# 09_Misc.net
KiCad netlist of a schematic drawn in Altium Designer
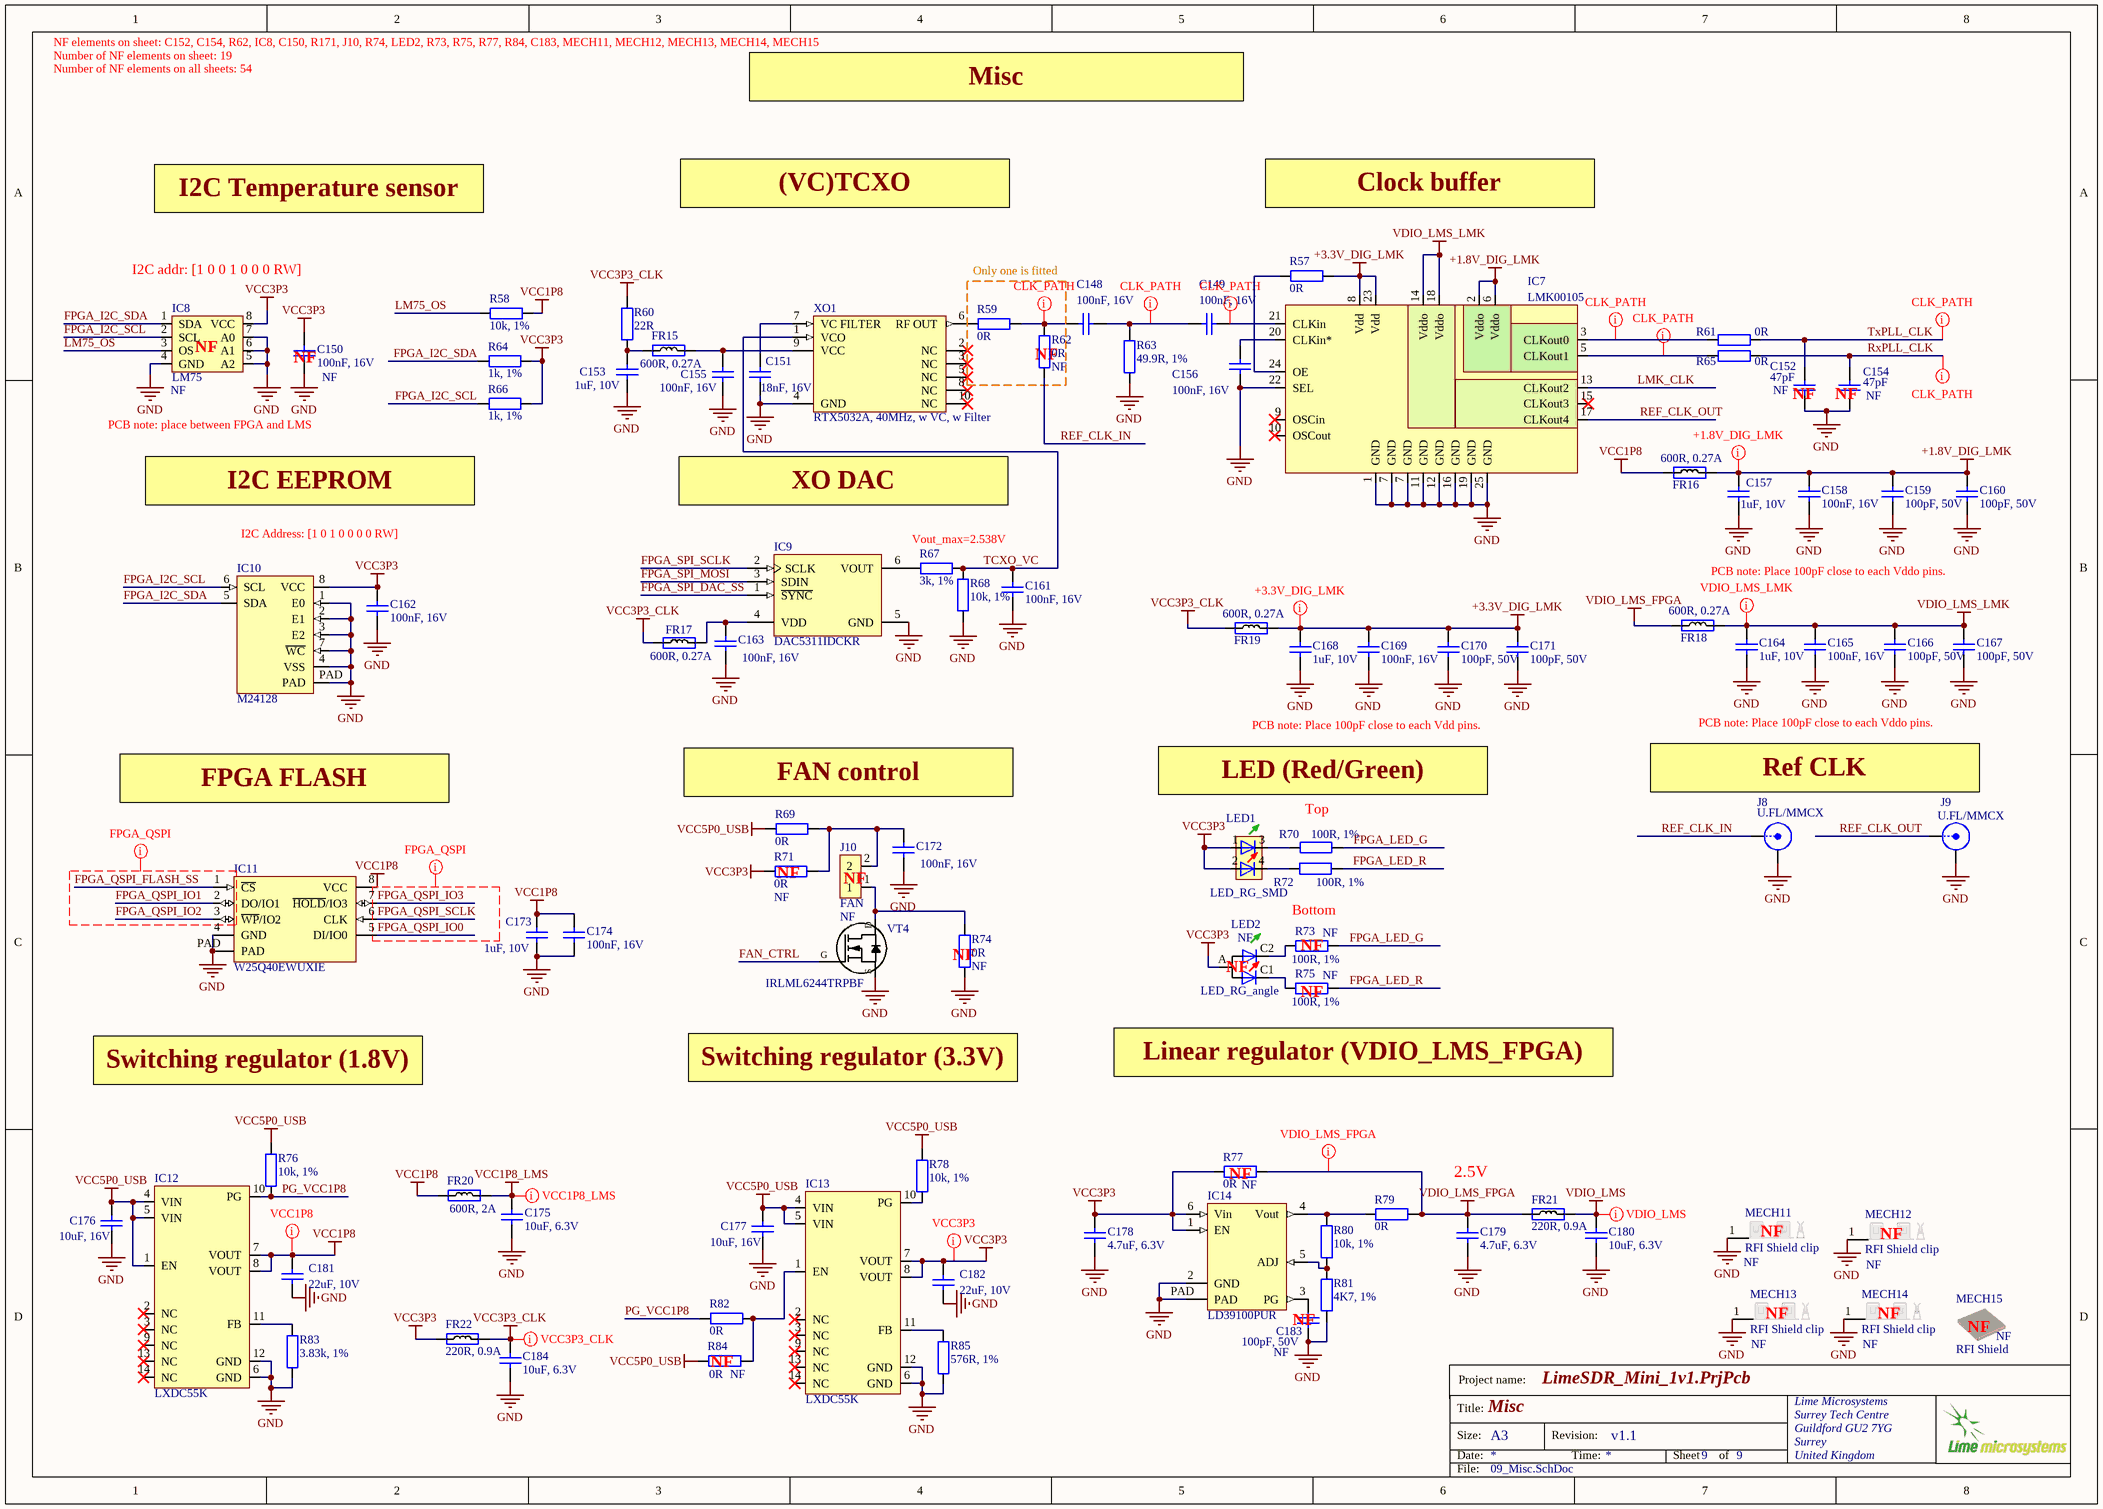
[diagram p0: 09_Misc.SchDoc]

(export (version "E")
  (design (tool "Eeschema 10.0.6"))
  (components
    (comp (ref "C148")
      (value "100nF, 16V")
      (footprint "CAP0402")
      (fields
        (field (name "MANUFACTURER") "Murata Electronics")
        (field (name "TOLERANCE") "10 %")
        (field (name "MANUFACTURER PART NUMBER") "GRM155R71C104KA88D")
      )
      (libsource (lib "LimeMicroAltiumLib_schLib") (part "Cap_0402"))
    )
    (comp (ref "C149")
      (value "100nF, 16V")
      (footprint "CAP0402")
      (fields
        (field (name "MANUFACTURER") "Murata Electronics")
        (field (name "TOLERANCE") "10 %")
        (field (name "MANUFACTURER PART NUMBER") "GRM155R71C104KA88D")
      )
      (libsource (lib "LimeMicroAltiumLib_schLib") (part "Cap_0402"))
    )
    (comp (ref "C150")
      (value "100nF, 16V")
      (footprint "CAP0402")
      (fields
        (field (name "TOLERANCE") "10 %")
        (field (name "MANUFACTURER") "Murata Electronics")
        (field (name "MANUFACTURER PART NUMBER") "GRM155R71C104KA88D")
        (field (name "ASSEMBLY INFO") "NF")
      )
      (libsource (lib "LimeFPGAboard_schLib") (part "Cap_0603"))
    )
    (comp (ref "C151")
      (value "18nF, 16V")
      (footprint "CAP0402")
      (fields (field (name "MANUFACTURER") "Yageo") (field (name "TOLERANCE") "±10%"))
      (libsource (lib "LimeMicroAltiumLib_schLib") (part "Cap_0402"))
    )
    (comp (ref "C152")
      (value "47pF")
      (footprint "CAP0402")
      (fields
        (field (name "TOLERANCE") "±1%")
        (field (name "MANUFACTURER") "TDK Corporation")
        (field (name "ASSEMBLY INFO") "NF")
      )
      (libsource (lib "LimeMicroAltiumLib_schLib") (part "Cap_0402"))
    )
    (comp (ref "C153")
      (value "1uF, 10V")
      (footprint "CAP0402")
      (fields (field (name "MANUFACTURER") "TDK"))
      (libsource (lib "LimeMicroAltiumLib_schLib") (part "Cap_0402"))
    )
    (comp (ref "C154")
      (value "47pF")
      (footprint "CAP0402")
      (fields
        (field (name "TOLERANCE") "±1%")
        (field (name "MANUFACTURER") "TDK Corporation")
        (field (name "ASSEMBLY INFO") "NF")
      )
      (libsource (lib "LimeMicroAltiumLib_schLib") (part "Cap_0402"))
    )
    (comp (ref "C155")
      (value "100nF, 16V")
      (footprint "CAP0402")
      (fields
        (field (name "MANUFACTURER") "Murata Electronics")
        (field (name "TOLERANCE") "10 %")
        (field (name "MANUFACTURER PART NUMBER") "GRM155R71C104KA88D")
      )
      (libsource (lib "LimeMicroAltiumLib_schLib") (part "Cap_0402"))
    )
    (comp (ref "C156")
      (value "100nF, 16V")
      (footprint "CAP0402")
      (fields
        (field (name "MANUFACTURER") "Murata Electronics")
        (field (name "TOLERANCE") "10 %")
        (field (name "MANUFACTURER PART NUMBER") "GRM155R71C104KA88D")
      )
      (libsource (lib "LimeMicroAltiumLib_schLib") (part "Cap_0402"))
    )
    (comp (ref "C157")
      (value "1uF, 10V")
      (footprint "CAP0402")
      (fields (field (name "MANUFACTURER") "TDK"))
      (libsource (lib "LimeMicroAltiumLib_schLib") (part "Cap_0402"))
    )
    (comp (ref "C158")
      (value "100nF, 16V")
      (footprint "CAP0402")
      (fields
        (field (name "MANUFACTURER") "Murata Electronics")
        (field (name "TOLERANCE") "10 %")
        (field (name "MANUFACTURER PART NUMBER") "GRM155R71C104KA88D")
      )
      (libsource (lib "LimeMicroAltiumLib_schLib") (part "Cap_0402"))
    )
    (comp (ref "C159")
      (value "100pF, 50V")
      (footprint "CAP0402")
      (fields (field (name "MANUFACTURER") "Yageo") (field (name "TOLERANCE") "±5%"))
      (libsource (lib "LimeMicroAltiumLib_schLib") (part "Cap_0402"))
    )
    (comp (ref "C160")
      (value "100pF, 50V")
      (footprint "CAP0402")
      (fields (field (name "MANUFACTURER") "Yageo") (field (name "TOLERANCE") "±5%"))
      (libsource (lib "LimeMicroAltiumLib_schLib") (part "Cap_0402"))
    )
    (comp (ref "C161")
      (value "100nF, 16V")
      (footprint "CAP0402")
      (fields
        (field (name "MANUFACTURER") "Murata Electronics")
        (field (name "TOLERANCE") "10 %")
        (field (name "MANUFACTURER PART NUMBER") "GRM155R71C104KA88D")
      )
      (libsource (lib "LimeMicroAltiumLib_schLib") (part "Cap_0402"))
    )
    (comp (ref "C162")
      (value "100nF, 16V")
      (footprint "CAP0402")
      (fields
        (field (name "TOLERANCE") "10 %")
        (field (name "MANUFACTURER") "Murata Electronics")
        (field (name "MANUFACTURER PART NUMBER") "GRM155R71C104KA88D")
      )
      (libsource (lib "LimeFPGAboard_schLib") (part "Cap_0603"))
    )
    (comp (ref "C163")
      (value "100nF, 16V")
      (footprint "CAP0402")
      (fields
        (field (name "TOLERANCE") "10 %")
        (field (name "MANUFACTURER") "Murata Electronics")
        (field (name "MANUFACTURER PART NUMBER") "GRM155R71C104KA88D")
      )
      (libsource (lib "LimeFPGAboard_schLib") (part "Cap_0603"))
    )
    (comp (ref "C164")
      (value "1uF, 10V")
      (footprint "CAP0402")
      (fields (field (name "MANUFACTURER") "TDK"))
      (libsource (lib "LimeMicroAltiumLib_schLib") (part "Cap_0402"))
    )
    (comp (ref "C165")
      (value "100nF, 16V")
      (footprint "CAP0402")
      (fields
        (field (name "MANUFACTURER") "Murata Electronics")
        (field (name "TOLERANCE") "10 %")
        (field (name "MANUFACTURER PART NUMBER") "GRM155R71C104KA88D")
      )
      (libsource (lib "LimeMicroAltiumLib_schLib") (part "Cap_0402"))
    )
    (comp (ref "C166")
      (value "100pF, 50V")
      (footprint "CAP0402")
      (fields (field (name "MANUFACTURER") "Yageo") (field (name "TOLERANCE") "±5%"))
      (libsource (lib "LimeMicroAltiumLib_schLib") (part "Cap_0402"))
    )
    (comp (ref "C167")
      (value "100pF, 50V")
      (footprint "CAP0402")
      (fields (field (name "MANUFACTURER") "Yageo") (field (name "TOLERANCE") "±5%"))
      (libsource (lib "LimeMicroAltiumLib_schLib") (part "Cap_0402"))
    )
    (comp (ref "C168")
      (value "1uF, 10V")
      (footprint "CAP0402")
      (fields (field (name "MANUFACTURER") "TDK"))
      (libsource (lib "LimeMicroAltiumLib_schLib") (part "Cap_0402"))
    )
    (comp (ref "C169")
      (value "100nF, 16V")
      (footprint "CAP0402")
      (fields
        (field (name "MANUFACTURER") "Murata Electronics")
        (field (name "TOLERANCE") "10 %")
        (field (name "MANUFACTURER PART NUMBER") "GRM155R71C104KA88D")
      )
      (libsource (lib "LimeMicroAltiumLib_schLib") (part "Cap_0402"))
    )
    (comp (ref "C170")
      (value "100pF, 50V")
      (footprint "CAP0402")
      (fields (field (name "MANUFACTURER") "Yageo") (field (name "TOLERANCE") "±5%"))
      (libsource (lib "LimeMicroAltiumLib_schLib") (part "Cap_0402"))
    )
    (comp (ref "C171")
      (value "100pF, 50V")
      (footprint "CAP0402")
      (fields (field (name "MANUFACTURER") "Yageo") (field (name "TOLERANCE") "±5%"))
      (libsource (lib "LimeMicroAltiumLib_schLib") (part "Cap_0402"))
    )
    (comp (ref "C172")
      (value "100nF, 16V")
      (footprint "CAP0402")
      (fields
        (field (name "TOLERANCE") "10 %")
        (field (name "MANUFACTURER") "Murata Electronics")
        (field (name "MANUFACTURER PART NUMBER") "GRM155R71C104KA88D")
      )
      (libsource (lib "LimeFPGAboard_schLib") (part "Cap_0603"))
    )
    (comp (ref "C173")
      (value "1uF, 10V")
      (footprint "CAP0402")
      (fields (field (name "MANUFACTURER") "TDK"))
      (libsource (lib "LimeMicroAltiumLib_schLib") (part "Cap_0402"))
    )
    (comp (ref "C174")
      (value "100nF, 16V")
      (footprint "CAP0402")
      (fields
        (field (name "TOLERANCE") "10 %")
        (field (name "MANUFACTURER") "Murata Electronics")
        (field (name "MANUFACTURER PART NUMBER") "GRM155R71C104KA88D")
      )
      (libsource (lib "LimeFPGAboard_schLib") (part "Cap_0603"))
    )
    (comp (ref "C175")
      (value "10uF, 6.3V")
      (footprint "CAP0603")
      (fields (field (name "TOLERANCE") "±20%") (field (name "MANUFACTURER") "Yageo"))
      (libsource (lib "LimeFPGAboard_schLib") (part "Cap_0603"))
    )
    (comp (ref "C176")
      (value "10uF, 16V")
      (footprint "CAP0603")
      (fields (field (name "MANUFACTURER") "Yageo") (field (name "TOLERANCE") "±20%"))
      (libsource (lib "LimeMicroAltiumLib_schLib") (part "Cap_0603"))
    )
    (comp (ref "C177")
      (value "10uF, 16V")
      (footprint "CAP0603")
      (fields (field (name "MANUFACTURER") "Yageo") (field (name "TOLERANCE") "±20%"))
      (libsource (lib "LimeMicroAltiumLib_schLib") (part "Cap_0603"))
    )
    (comp (ref "C178")
      (value "4.7uF, 6.3V")
      (footprint "CAP0402")
      (fields
        (field (name "MANUFACTURER") "Murata Electronics North America")
        (field (name "TOLERANCE") "±20%")
        (field (name "MANUFACTURER PART NUMBER") "GRM155R60J475ME87D")
      )
      (libsource (lib "LimeMicroAltiumLib_schLib") (part "Cap_0402"))
    )
    (comp (ref "C179")
      (value "4.7uF, 6.3V")
      (footprint "CAP0402")
      (fields
        (field (name "MANUFACTURER") "Murata Electronics North America")
        (field (name "TOLERANCE") "±20%")
        (field (name "MANUFACTURER PART NUMBER") "GRM155R60J475ME87D")
      )
      (libsource (lib "LimeMicroAltiumLib_schLib") (part "Cap_0402"))
    )
    (comp (ref "C180")
      (value "10uF, 6.3V")
      (footprint "CAP0603")
      (fields (field (name "TOLERANCE") "±20%") (field (name "MANUFACTURER") "Yageo"))
      (libsource (lib "LimeFPGAboard_schLib") (part "Cap_0603"))
    )
    (comp (ref "C181")
      (value "22uF, 10V")
      (footprint "CAP0603")
      (fields (field (name "TOLERANCE") "20 %") (field (name "MANUFACTURER") "TDK Corporation"))
      (libsource (lib "LimeFPGAboard_schLib") (part "Cap_0603"))
    )
    (comp (ref "C182")
      (value "22uF, 10V")
      (footprint "CAP0603")
      (fields (field (name "TOLERANCE") "20 %") (field (name "MANUFACTURER") "TDK Corporation"))
      (libsource (lib "LimeFPGAboard_schLib") (part "Cap_0603"))
    )
    (comp (ref "C183")
      (value "100pF, 50V")
      (footprint "CAP0402")
      (fields
        (field (name "ASSEMBLY INFO") "NF")
        (field (name "MANUFACTURER") "Yageo")
        (field (name "TOLERANCE") "±5%")
      )
      (libsource (lib "LimeMicroAltiumLib_schLib") (part "Cap_0402"))
    )
    (comp (ref "C184")
      (value "10uF, 6.3V")
      (footprint "CAP0603")
      (fields (field (name "TOLERANCE") "±20%") (field (name "MANUFACTURER") "Yageo"))
      (libsource (lib "LimeFPGAboard_schLib") (part "Cap_0603"))
    )
    (comp (ref "FR15")
      (value "600R, 0.27A")
      (footprint "RES0201")
      (fields (field (name "MANUFACTURER") "Taiyo Yuden"))
      (libsource (lib "LimeMicroAltiumLib_schLib") (part "Ferrite"))
    )
    (comp (ref "FR16")
      (value "600R, 0.27A")
      (footprint "RES0201")
      (fields (field (name "MANUFACTURER") "Taiyo Yuden"))
      (libsource (lib "LimeMicroAltiumLib_schLib") (part "Ferrite"))
    )
    (comp (ref "FR17")
      (value "600R, 0.27A")
      (footprint "RES0201")
      (fields (field (name "MANUFACTURER") "Taiyo Yuden"))
      (libsource (lib "LimeMicroAltiumLib_schLib") (part "Ferrite"))
    )
    (comp (ref "FR18")
      (value "600R, 0.27A")
      (footprint "RES0201")
      (fields (field (name "MANUFACTURER") "Taiyo Yuden"))
      (libsource (lib "LimeMicroAltiumLib_schLib") (part "Ferrite"))
    )
    (comp (ref "FR19")
      (value "600R, 0.27A")
      (footprint "RES0201")
      (fields (field (name "MANUFACTURER") "Taiyo Yuden"))
      (libsource (lib "LimeMicroAltiumLib_schLib") (part "Ferrite"))
    )
    (comp (ref "FR20")
      (value "600R, 2A")
      (footprint "RES0805")
      (fields (field (name "MANUFACTURER") "TDK Corporation"))
      (libsource (lib "LimeMicroAltiumLib_schLib") (part "Ferrite"))
    )
    (comp (ref "FR21")
      (value "220R, 0.9A")
      (footprint "RES0402")
      (fields (field (name "MANUFACTURER") "TDK Corporation"))
      (libsource (lib "LimeFPGAboard_schLib") (part "Ferrite"))
    )
    (comp (ref "FR22")
      (value "220R, 0.9A")
      (footprint "RES0402")
      (fields (field (name "MANUFACTURER") "TDK Corporation"))
      (libsource (lib "LimeFPGAboard_schLib") (part "Ferrite"))
    )
    (comp (ref "IC7")
      (value "LMK00105")
      (footprint "LMK00105SQ")
      (fields (field (name "MANUFACTURER") "Texas Instruments"))
      (libsource (lib "LimeMicroAltiumLib_schLib") (part "LMK00105"))
    )
    (comp (ref "IC8")
      (value "LM75")
      (footprint "HWSON8_LM75")
      (fields
        (field (name "MANUFACTURER") "NXP Semiconductors")
        (field (name "MANUFACTURER PART NUMBER") "LM75BTP,147")
        (field (name "ASSEMBLY INFO") "NF")
      )
      (libsource (lib "LimeMicroAltiumLib_schLib") (part "LM75"))
    )
    (comp (ref "IC9")
      (value "DAC5311IDCKR")
      (footprint "AD5601_SOT23-6")
      (fields (field (name "MANUFACTURER") "Texas Instruments"))
      (libsource (lib "LimeMicroAltiumLib_schLib") (part "AD5601BKSZ-REEL7"))
    )
    (comp (ref "IC10")
      (value "M24128")
      (footprint "M24128-DFMC6TG")
      (fields (field (name "MANUFACTURER") "STMicroelectronics"))
      (libsource (lib "LimeMicroAltiumLib_schLib") (part "M24128-DFMC6TG"))
    )
    (comp (ref "IC11")
      (value "W25Q40EWUXIE")
      (footprint "W25Q40EWUXIE_8-USON")
      (fields (field (name "MANUFACTURER") "Winbond Electronics"))
      (libsource (lib "LimeMicroAltiumLib_schLib") (part "W25Q40EWUXIE"))
    )
    (comp (ref "IC12")
      (value "LXDC55K")
      (footprint "LXDC55K")
      (description "LXDC55KAAA-205")
      (fields (field (name "MANUFACTURER") "Murata Electronics North America"))
      (libsource (lib "LimeMicroAltiumLib_schLib") (part "LXDC55K"))
    )
    (comp (ref "IC13")
      (value "LXDC55K")
      (footprint "LXDC55K")
      (description "LXDC55KAAA-205")
      (fields (field (name "MANUFACTURER") "Murata Electronics North America"))
      (libsource (lib "LimeMicroAltiumLib_schLib") (part "LXDC55K"))
    )
    (comp (ref "IC14")
      (value "LD39100PUR")
      (footprint "LD39100PUR")
      (fields (field (name "MANUFACTURER") "STMicroelectronics"))
      (libsource (lib "LimeMicroAltiumLib_schLib") (part "LD39100PUR"))
    )
    (comp (ref "J8")
      (value "U.FL/MMCX")
      (footprint "MMCX_UFL_conn_u")
      (description "CONN UMC RCPT STR 50 OHM SMD")
      (fields (field (name "MANUFACTURER") "Molex, LLC"))
      (libsource (lib "LimeMicroAltiumLib_schLib") (part "RF_IF_connector"))
    )
    (comp (ref "J9")
      (value "U.FL/MMCX")
      (footprint "MMCX_UFL_conn_u")
      (description "CONN UMC RCPT STR 50 OHM SMD")
      (fields (field (name "MANUFACTURER") "Molex, LLC"))
      (libsource (lib "LimeMicroAltiumLib_schLib") (part "RF_IF_connector"))
    )
    (comp (ref "J10")
      (value "FAN")
      (footprint "HDR_1x2_v2")
      (fields (field (name "ASSEMBLY INFO") "NF") (field (name "MANUFACTURER") "3M"))
      (libsource (lib "LimeFPGAboard_schLib") (part "Jumper"))
    )
    (comp (ref "LED1")
      (value "LED_RG_SMD")
      (footprint "LED-2x0603")
      (fields (field (name "MANUFACTURER") "Avago Technologies US Inc."))
      (libsource (lib "LimeMicroAltiumLib_schLib") (part "LED_green_red_SMD"))
    )
    (comp (ref "LED2")
      (value "LED_RG_angle")
      (footprint "LED_RG_RIGHT_ANGLE_v2")
      (description "160-2033-1-ND")
      (fields (field (name "MANUFACTURER") "Lite-On") (field (name "ASSEMBLY INFO") "NF"))
      (libsource (lib "LimeMicroAltiumLib_schLib") (part "LED_green_red_right_angle"))
    )
    (comp (ref "MECH11")
      (value "RFI Shield clip")
      (footprint "RFI_SHIELD_CLPS_MINI")
      (fields (field (name "MANUFACTURER") "HARWIN") (field (name "ASSEMBLY INFO") "NF"))
      (libsource (lib "LimeMicroAltiumLib_schLib") (part "RFI_SHIELD_CLIP"))
    )
    (comp (ref "MECH12")
      (value "RFI Shield clip")
      (footprint "RFI_SHIELD_CLPS_MINI")
      (fields (field (name "MANUFACTURER") "HARWIN") (field (name "ASSEMBLY INFO") "NF"))
      (libsource (lib "LimeMicroAltiumLib_schLib") (part "RFI_SHIELD_CLIP"))
    )
    (comp (ref "MECH13")
      (value "RFI Shield clip")
      (footprint "RFI_SHIELD_CLPS_MINI")
      (fields (field (name "MANUFACTURER") "HARWIN") (field (name "ASSEMBLY INFO") "NF"))
      (libsource (lib "LimeMicroAltiumLib_schLib") (part "RFI_SHIELD_CLIP"))
    )
    (comp (ref "MECH14")
      (value "RFI Shield clip")
      (footprint "RFI_SHIELD_CLPS_MINI")
      (fields (field (name "MANUFACTURER") "HARWIN") (field (name "ASSEMBLY INFO") "NF"))
      (libsource (lib "LimeMicroAltiumLib_schLib") (part "RFI_SHIELD_CLIP"))
    )
    (comp (ref "MECH15")
      (value "RFI Shield")
      (footprint "WurthElectronic_RF_shield")
      (fields (field (name "MANUFACTURER") "WURTH ELEKTRONIK") (field (name "ASSEMBLY INFO") "NF"))
      (libsource (lib "LimeMicroAltiumLib_schLib") (part "RFI_SHIELD_1"))
    )
    (comp (ref "R57")
      (value "0R")
      (footprint "RES0402")
      (fields (field (name "MANUFACTURER") "Yageo") (field (name "TOLERANCE") "Jumper"))
      (libsource (lib "LimeMicroAltiumLib_schLib") (part "Res_0402"))
    )
    (comp (ref "R58")
      (value "10k, 1%")
      (footprint "RES0402")
      (fields (field (name "MANUFACTURER") "Yageo") (field (name "TOLERANCE") "±1%"))
      (libsource (lib "LimeMicroAltiumLib_schLib") (part "Res_0402"))
    )
    (comp (ref "R59")
      (value "0R")
      (footprint "RES0402")
      (fields (field (name "MANUFACTURER") "Yageo") (field (name "TOLERANCE") "Jumper"))
      (libsource (lib "LimeMicroAltiumLib_schLib") (part "Res_0402"))
    )
    (comp (ref "R60")
      (value "22R")
      (footprint "RES0402")
      (fields (field (name "TOLERANCE") "±1%") (field (name "MANUFACTURER") "Yageo"))
      (libsource (lib "LimeFPGAboard_schLib") (part "Res_0402"))
    )
    (comp (ref "R61")
      (value "0R")
      (footprint "RES0402")
      (fields (field (name "MANUFACTURER") "Yageo"))
      (libsource (lib "LimeFPGAboard_schLib") (part "Res_0402"))
    )
    (comp (ref "R62")
      (value "0R")
      (footprint "RES0402")
      (fields
        (field (name "ASSEMBLY INFO") "NF")
        (field (name "MANUFACTURER") "Yageo")
        (field (name "TOLERANCE") "Jumper")
      )
      (libsource (lib "LimeMicroAltiumLib_schLib") (part "Res_0402"))
    )
    (comp (ref "R63")
      (value "49.9R, 1%")
      (footprint "RES0402")
      (fields
        (field (name "TOLERANCE") "±1%")
        (field (name "MANUFACTURER") "Samsung Electro-Mechanics America, Inc.")
        (field (name "MANUFACTURER PART NUMBER") "RC1005F49R9CS")
      )
      (libsource (lib "LimeMicroAltiumLib_schLib") (part "Res_0402"))
    )
    (comp (ref "R64")
      (value "1k, 1%")
      (footprint "RES0402")
      (fields (field (name "MANUFACTURER") "Stackpole Electronics Inc") (field (name "TOLERANCE") "±1%"))
      (libsource (lib "LimeMicroAltiumLib_schLib") (part "Res_0402"))
    )
    (comp (ref "R65")
      (value "0R")
      (footprint "RES0402")
      (fields (field (name "MANUFACTURER") "Yageo"))
      (libsource (lib "LimeFPGAboard_schLib") (part "Res_0402"))
    )
    (comp (ref "R66")
      (value "1k, 1%")
      (footprint "RES0402")
      (fields (field (name "MANUFACTURER") "Stackpole Electronics Inc") (field (name "TOLERANCE") "±1%"))
      (libsource (lib "LimeMicroAltiumLib_schLib") (part "Res_0402"))
    )
    (comp (ref "R67")
      (value "3k, 1%")
      (footprint "RES0402")
      (fields (field (name "TOLERANCE") "±1%") (field (name "MANUFACTURER") "Vishay Dale"))
      (libsource (lib "LimeMicroAltiumLib_schLib") (part "Res_0402"))
    )
    (comp (ref "R68")
      (value "10k, 1%")
      (footprint "RES0402")
      (fields (field (name "MANUFACTURER") "Yageo") (field (name "TOLERANCE") "±1%"))
      (libsource (lib "LimeMicroAltiumLib_schLib") (part "Res_0402"))
    )
    (comp (ref "R69")
      (value "0R")
      (footprint "RES0402")
      (fields (field (name "MANUFACTURER") "Yageo") (field (name "TOLERANCE") "Jumper"))
      (libsource (lib "LimeMicroAltiumLib_schLib") (part "Res_0402"))
    )
    (comp (ref "R70")
      (value "100R, 1%")
      (footprint "RES0402")
      (fields (field (name "TOLERANCE") "±1%") (field (name "MANUFACTURER") "Stackpole Electronics Inc."))
      (libsource (lib "LimeMicroAltiumLib_schLib") (part "Res_0402"))
    )
    (comp (ref "R71")
      (value "0R")
      (footprint "RES0402")
      (fields
        (field (name "ASSEMBLY INFO") "NF")
        (field (name "MANUFACTURER") "Yageo")
        (field (name "TOLERANCE") "Jumper")
      )
      (libsource (lib "LimeMicroAltiumLib_schLib") (part "Res_0402"))
    )
    (comp (ref "R72")
      (value "100R, 1%")
      (footprint "RES0402")
      (fields (field (name "TOLERANCE") "±1%") (field (name "MANUFACTURER") "Stackpole Electronics Inc."))
      (libsource (lib "LimeMicroAltiumLib_schLib") (part "Res_0402"))
    )
    (comp (ref "R73")
      (value "100R, 1%")
      (footprint "RES0402")
      (fields
        (field (name "TOLERANCE") "±1%")
        (field (name "MANUFACTURER") "Stackpole Electronics Inc.")
        (field (name "ASSEMBLY INFO") "NF")
      )
      (libsource (lib "LimeMicroAltiumLib_schLib") (part "Res_0402"))
    )
    (comp (ref "R74")
      (value "0R")
      (footprint "RES0402")
      (fields
        (field (name "ASSEMBLY INFO") "NF")
        (field (name "MANUFACTURER") "Yageo")
        (field (name "TOLERANCE") "Jumper")
      )
      (libsource (lib "LimeMicroAltiumLib_schLib") (part "Res_0402"))
    )
    (comp (ref "R75")
      (value "100R, 1%")
      (footprint "RES0402")
      (fields
        (field (name "TOLERANCE") "±1%")
        (field (name "MANUFACTURER") "Stackpole Electronics Inc.")
        (field (name "ASSEMBLY INFO") "NF")
      )
      (libsource (lib "LimeMicroAltiumLib_schLib") (part "Res_0402"))
    )
    (comp (ref "R76")
      (value "10k, 1%")
      (footprint "RES0402")
      (fields (field (name "MANUFACTURER") "Yageo") (field (name "TOLERANCE") "±1%"))
      (libsource (lib "LimeMicroAltiumLib_schLib") (part "Res_0402"))
    )
    (comp (ref "R77")
      (value "0R")
      (footprint "RES0402")
      (fields (field (name "MANUFACTURER") "Yageo") (field (name "ASSEMBLY INFO") "NF"))
      (libsource (lib "LimeFPGAboard_schLib") (part "Res_0402"))
    )
    (comp (ref "R78")
      (value "10k, 1%")
      (footprint "RES0402")
      (fields (field (name "MANUFACTURER") "Yageo") (field (name "TOLERANCE") "±1%"))
      (libsource (lib "LimeMicroAltiumLib_schLib") (part "Res_0402"))
    )
    (comp (ref "R79")
      (value "0R")
      (footprint "RES0402")
      (fields (field (name "MANUFACTURER") "Yageo"))
      (libsource (lib "LimeFPGAboard_schLib") (part "Res_0402"))
    )
    (comp (ref "R80")
      (value "10k, 1%")
      (footprint "RES0402")
      (fields (field (name "MANUFACTURER") "Yageo") (field (name "TOLERANCE") "±1%"))
      (libsource (lib "LimeMicroAltiumLib_schLib") (part "Res_0402"))
    )
    (comp (ref "R81")
      (value "4K7, 1%")
      (footprint "RES0402")
      (fields (field (name "MANUFACTURER") "Yageo") (field (name "TOLERANCE") "±1%"))
      (libsource (lib "LimeFPGAboard_schLib") (part "Res_0402"))
    )
    (comp (ref "R82")
      (value "0R")
      (footprint "RES0402")
      (fields (field (name "MANUFACTURER") "Yageo") (field (name "TOLERANCE") "Jumper"))
      (libsource (lib "LimeMicroAltiumLib_schLib") (part "Res_0402"))
    )
    (comp (ref "R83")
      (value "3.83k, 1%")
      (footprint "RES0402")
      (fields (field (name "TOLERANCE") "±1%") (field (name "MANUFACTURER") "Stackpole Electronics Inc."))
      (libsource (lib "LimeMicroAltiumLib_schLib") (part "Res_0402"))
    )
    (comp (ref "R84")
      (value "0R")
      (footprint "RES0402")
      (fields
        (field (name "ASSEMBLY INFO") "NF")
        (field (name "MANUFACTURER") "Yageo")
        (field (name "TOLERANCE") "Jumper")
      )
      (libsource (lib "LimeMicroAltiumLib_schLib") (part "Res_0402"))
    )
    (comp (ref "R85")
      (value "576R, 1%")
      (footprint "RES0402")
      (fields (field (name "TOLERANCE") "±1%") (field (name "MANUFACTURER") "Yageo"))
      (libsource (lib "LimeMicroAltiumLib_schLib") (part "Res_0402"))
    )
    (comp (ref "VT4")
      (value "IRLML6244TRPBF")
      (footprint "SOT23-3")
      (description "NDS331N")
      (fields (field (name "MANUFACTURER") "Infineon Technologies"))
      (libsource (lib "LimeFPGAboard_schLib") (part "NDS331N"))
    )
    (comp (ref "XO1")
      (value "RTX5032A, 40MHz, w VC, w Filter")
      (footprint "RAKON_RTX5032A")
      (fields (field (name "MANUFACTURER") "Rakon"))
      (libsource (lib "LimeMicroAltiumLib_schLib") (part "Rakon_RTX5032A"))
    )
  )
  (nets
    (net (code "1") (name "+1.8V_DIG_LMK") (class "Default")
      (node (ref "C157") (pin "2") (pinfunction "2_2") (pintype "passive"))
      (node (ref "C158") (pin "2") (pinfunction "2_2") (pintype "passive"))
      (node (ref "C159") (pin "2") (pinfunction "2_2") (pintype "passive"))
      (node (ref "C160") (pin "2") (pinfunction "2_2") (pintype "passive"))
      (node (ref "FR16") (pin "2") (pinfunction "2_2") (pintype "passive"))
      (node (ref "IC7") (pin "2") (pinfunction "Vddo_2") (pintype "passive"))
      (node (ref "IC7") (pin "6") (pinfunction "Vddo_6") (pintype "passive"))
    )
    (net (code "2") (name "+3.3V_DIG_LMK") (class "Default")
      (node (ref "C168") (pin "2") (pinfunction "2_2") (pintype "passive"))
      (node (ref "C169") (pin "2") (pinfunction "2_2") (pintype "passive"))
      (node (ref "C170") (pin "2") (pinfunction "2_2") (pintype "passive"))
      (node (ref "C171") (pin "2") (pinfunction "2_2") (pintype "passive"))
      (node (ref "FR19") (pin "2") (pinfunction "2_2") (pintype "passive"))
      (node (ref "IC7") (pin "23") (pinfunction "Vdd_23") (pintype "passive"))
      (node (ref "IC7") (pin "8") (pinfunction "Vdd_8") (pintype "passive"))
      (node (ref "R57") (pin "2") (pinfunction "2_2") (pintype "passive"))
    )
    (net (code "3") (name "/FAN_CTRL") (class "Default")
      (node (ref "VT4") (pin "G") (pinfunction "G_G") (pintype "passive"))
    )
    (net (code "4") (name "/FPGA_I2C_SCL") (class "Default")
      (node (ref "IC10") (pin "6") (pinfunction "SCL_6") (pintype "input"))
      (node (ref "IC8") (pin "2") (pinfunction "SCL_2") (pintype "passive"))
      (node (ref "R66") (pin "2") (pinfunction "2_2") (pintype "passive"))
    )
    (net (code "5") (name "/FPGA_I2C_SDA") (class "Default")
      (node (ref "IC10") (pin "5") (pinfunction "SDA_5") (pintype "bidirectional"))
      (node (ref "IC8") (pin "1") (pinfunction "SDA_1") (pintype "passive"))
      (node (ref "R64") (pin "2") (pinfunction "2_2") (pintype "passive"))
    )
    (net (code "6") (name "/FPGA_LED_G") (class "Default")
      (node (ref "R70") (pin "2") (pinfunction "2_2") (pintype "passive"))
      (node (ref "R73") (pin "2") (pinfunction "2_2") (pintype "passive"))
    )
    (net (code "7") (name "/FPGA_LED_R") (class "Default")
      (node (ref "R72") (pin "2") (pinfunction "2_2") (pintype "passive"))
      (node (ref "R75") (pin "2") (pinfunction "2_2") (pintype "passive"))
    )
    (net (code "8") (name "/FPGA_QSPI_FLASH_SS") (class "Default")
      (node (ref "IC11") (pin "1") (pinfunction "~{CS}_1") (pintype "input"))
    )
    (net (code "9") (name "/FPGA_QSPI_IO0") (class "Default")
      (node (ref "IC11") (pin "5") (pinfunction "DI/IO0_5") (pintype "passive"))
    )
    (net (code "10") (name "/FPGA_QSPI_IO1") (class "Default")
      (node (ref "IC11") (pin "2") (pinfunction "DO/IO1_2") (pintype "bidirectional"))
    )
    (net (code "11") (name "/FPGA_QSPI_IO2") (class "Default")
      (node (ref "IC11") (pin "3") (pinfunction "~{WP}/IO2_3") (pintype "bidirectional"))
    )
    (net (code "12") (name "/FPGA_QSPI_IO3") (class "Default")
      (node (ref "IC11") (pin "7") (pinfunction "~{HOLD}/IO3_7") (pintype "bidirectional"))
    )
    (net (code "13") (name "/FPGA_QSPI_SCLK") (class "Default")
      (node (ref "IC11") (pin "6") (pinfunction "CLK_6") (pintype "input"))
    )
    (net (code "14") (name "/FPGA_SPI_DAC_SS") (class "Default")
      (node (ref "IC9") (pin "1") (pinfunction "~{SYNC}_1") (pintype "input"))
    )
    (net (code "15") (name "/FPGA_SPI_MOSI") (class "Default")
      (node (ref "IC9") (pin "3") (pinfunction "SDIN_3") (pintype "input"))
    )
    (net (code "16") (name "/FPGA_SPI_SCLK") (class "Default")
      (node (ref "IC9") (pin "2") (pinfunction "SCLK_2") (pintype "input"))
    )
    (net (code "17") (name "/LM75_OS") (class "Default")
      (node (ref "IC8") (pin "3") (pinfunction "OS_3") (pintype "passive"))
      (node (ref "R58") (pin "1") (pinfunction "1_1") (pintype "passive"))
    )
    (net (code "18") (name "/LMK_CLK") (class "Default")
      (node (ref "IC7") (pin "13") (pinfunction "CLKout2_13") (pintype "passive"))
    )
    (net (code "19") (name "/PG_VCC1P8") (class "Default")
      (node (ref "IC12") (pin "10") (pinfunction "PG_10") (pintype "passive"))
      (node (ref "R76") (pin "1") (pinfunction "1_1") (pintype "passive"))
      (node (ref "R82") (pin "2") (pinfunction "2_2") (pintype "passive"))
    )
    (net (code "20") (name "/REF_CLK_IN") (class "Default")
      (node (ref "J8") (pin "1") (pinfunction "X_1") (pintype "passive"))
      (node (ref "R62") (pin "1") (pinfunction "1_1") (pintype "passive"))
    )
    (net (code "21") (name "/REF_CLK_OUT") (class "Default")
      (node (ref "IC7") (pin "17") (pinfunction "CLKout4_17") (pintype "passive"))
      (node (ref "J9") (pin "1") (pinfunction "X_1") (pintype "passive"))
    )
    (net (code "22") (name "/RxPLL_CLK") (class "Default")
      (node (ref "C154") (pin "2") (pinfunction "2_2") (pintype "passive"))
      (node (ref "R65") (pin "1") (pinfunction "1_1") (pintype "passive"))
    )
    (net (code "23") (name "/TCXO_VC") (class "Default")
      (node (ref "C161") (pin "2") (pinfunction "2_2") (pintype "passive"))
      (node (ref "R67") (pin "1") (pinfunction "1_1") (pintype "passive"))
      (node (ref "R68") (pin "1") (pinfunction "1_1") (pintype "passive"))
      (node (ref "XO1") (pin "1") (pinfunction "VCO_1") (pintype "input"))
    )
    (net (code "24") (name "/TxPLL_CLK") (class "Default")
      (node (ref "C152") (pin "2") (pinfunction "2_2") (pintype "passive"))
      (node (ref "R61") (pin "1") (pinfunction "1_1") (pintype "passive"))
    )
    (net (code "25") (name "GND") (class "Default")
      (node (ref "C150") (pin "2") (pinfunction "2_2") (pintype "passive"))
      (node (ref "C151") (pin "1") (pinfunction "1_1") (pintype "passive"))
      (node (ref "C152") (pin "1") (pinfunction "1_1") (pintype "passive"))
      (node (ref "C153") (pin "1") (pinfunction "1_1") (pintype "passive"))
      (node (ref "C154") (pin "1") (pinfunction "1_1") (pintype "passive"))
      (node (ref "C155") (pin "1") (pinfunction "1_1") (pintype "passive"))
      (node (ref "C156") (pin "1") (pinfunction "1_1") (pintype "passive"))
      (node (ref "C157") (pin "1") (pinfunction "1_1") (pintype "passive"))
      (node (ref "C158") (pin "1") (pinfunction "1_1") (pintype "passive"))
      (node (ref "C159") (pin "1") (pinfunction "1_1") (pintype "passive"))
      (node (ref "C160") (pin "1") (pinfunction "1_1") (pintype "passive"))
      (node (ref "C161") (pin "1") (pinfunction "1_1") (pintype "passive"))
      (node (ref "C162") (pin "2") (pinfunction "2_2") (pintype "passive"))
      (node (ref "C163") (pin "2") (pinfunction "2_2") (pintype "passive"))
      (node (ref "C164") (pin "1") (pinfunction "1_1") (pintype "passive"))
      (node (ref "C165") (pin "1") (pinfunction "1_1") (pintype "passive"))
      (node (ref "C166") (pin "1") (pinfunction "1_1") (pintype "passive"))
      (node (ref "C167") (pin "1") (pinfunction "1_1") (pintype "passive"))
      (node (ref "C168") (pin "1") (pinfunction "1_1") (pintype "passive"))
      (node (ref "C169") (pin "1") (pinfunction "1_1") (pintype "passive"))
      (node (ref "C170") (pin "1") (pinfunction "1_1") (pintype "passive"))
      (node (ref "C171") (pin "1") (pinfunction "1_1") (pintype "passive"))
      (node (ref "C172") (pin "2") (pinfunction "2_2") (pintype "passive"))
      (node (ref "C173") (pin "1") (pinfunction "1_1") (pintype "passive"))
      (node (ref "C174") (pin "2") (pinfunction "2_2") (pintype "passive"))
      (node (ref "C175") (pin "1") (pinfunction "1_1") (pintype "passive"))
      (node (ref "C176") (pin "1") (pinfunction "1_1") (pintype "passive"))
      (node (ref "C177") (pin "1") (pinfunction "1_1") (pintype "passive"))
      (node (ref "C178") (pin "1") (pinfunction "1_1") (pintype "passive"))
      (node (ref "C179") (pin "1") (pinfunction "1_1") (pintype "passive"))
      (node (ref "C180") (pin "1") (pinfunction "1_1") (pintype "passive"))
      (node (ref "C181") (pin "1") (pinfunction "1_1") (pintype "passive"))
      (node (ref "C182") (pin "1") (pinfunction "1_1") (pintype "passive"))
      (node (ref "C183") (pin "1") (pinfunction "1_1") (pintype "passive"))
      (node (ref "C184") (pin "1") (pinfunction "1_1") (pintype "passive"))
      (node (ref "IC10") (pin "1") (pinfunction "E0_1") (pintype "input"))
      (node (ref "IC10") (pin "2") (pinfunction "E1_2") (pintype "input"))
      (node (ref "IC10") (pin "3") (pinfunction "E2_3") (pintype "input"))
      (node (ref "IC10") (pin "4") (pinfunction "VSS_4") (pintype "power_in"))
      (node (ref "IC10") (pin "7") (pinfunction "~{WC}_7") (pintype "input"))
      (node (ref "IC10") (pin "PAD") (pinfunction "PAD_PAD") (pintype "power_in"))
      (node (ref "IC11") (pin "4") (pinfunction "GND_4") (pintype "passive"))
      (node (ref "IC11") (pin "PAD") (pinfunction "PAD_PAD") (pintype "passive"))
      (node (ref "IC12") (pin "12") (pinfunction "GND_12") (pintype "passive"))
      (node (ref "IC12") (pin "6") (pinfunction "GND_6") (pintype "passive"))
      (node (ref "IC13") (pin "12") (pinfunction "GND_12") (pintype "passive"))
      (node (ref "IC13") (pin "6") (pinfunction "GND_6") (pintype "passive"))
      (node (ref "IC14") (pin "2") (pinfunction "GND_2") (pintype "passive"))
      (node (ref "IC14") (pin "PAD") (pinfunction "PAD_PAD") (pintype "passive"))
      (node (ref "IC7") (pin "1") (pinfunction "GND_1") (pintype "passive"))
      (node (ref "IC7") (pin "11") (pinfunction "GND_11") (pintype "passive"))
      (node (ref "IC7") (pin "12") (pinfunction "GND_12") (pintype "passive"))
      (node (ref "IC7") (pin "16") (pinfunction "GND_16") (pintype "passive"))
      (node (ref "IC7") (pin "19") (pinfunction "GND_19") (pintype "passive"))
      (node (ref "IC7") (pin "22") (pinfunction "SEL_22") (pintype "passive"))
      (node (ref "IC7") (pin "25") (pinfunction "GND_25") (pintype "passive"))
      (node (ref "IC7") (pin "7") (pinfunction "GND_7") (pintype "passive"))
      (node (ref "IC8") (pin "4") (pinfunction "GND_4") (pintype "passive"))
      (node (ref "IC8") (pin "5") (pinfunction "A2_5") (pintype "passive"))
      (node (ref "IC8") (pin "6") (pinfunction "A1_6") (pintype "passive"))
      (node (ref "IC8") (pin "7") (pinfunction "A0_7") (pintype "passive"))
      (node (ref "IC9") (pin "5") (pinfunction "GND_5") (pintype "power_in"))
      (node (ref "J8") (pin "2") (pinfunction "Y_2") (pintype "passive"))
      (node (ref "J9") (pin "2") (pinfunction "Y_2") (pintype "passive"))
      (node (ref "MECH11") (pin "1") (pinfunction "GND_1") (pintype "passive"))
      (node (ref "MECH12") (pin "1") (pinfunction "GND_1") (pintype "passive"))
      (node (ref "MECH13") (pin "1") (pinfunction "GND_1") (pintype "passive"))
      (node (ref "MECH14") (pin "1") (pinfunction "GND_1") (pintype "passive"))
      (node (ref "R63") (pin "1") (pinfunction "1_1") (pintype "passive"))
      (node (ref "R68") (pin "2") (pinfunction "2_2") (pintype "passive"))
      (node (ref "R74") (pin "1") (pinfunction "1_1") (pintype "passive"))
      (node (ref "R81") (pin "2") (pinfunction "2_2") (pintype "passive"))
      (node (ref "R83") (pin "1") (pinfunction "1_1") (pintype "passive"))
      (node (ref "R85") (pin "1") (pinfunction "1_1") (pintype "passive"))
      (node (ref "VT4") (pin "S") (pinfunction "S_S") (pintype "passive"))
      (node (ref "XO1") (pin "4") (pinfunction "GND_4") (pintype "passive"))
    )
    (net (code "26") (name "Net-(C148-Pad1)") (class "Default")
      (node (ref "C148") (pin "1") (pinfunction "1_1") (pintype "passive"))
      (node (ref "C149") (pin "2") (pinfunction "2_2") (pintype "passive"))
      (node (ref "R63") (pin "2") (pinfunction "2_2") (pintype "passive"))
    )
    (net (code "27") (name "Net-(C148-Pad2)") (class "Default")
      (node (ref "C148") (pin "2") (pinfunction "2_2") (pintype "passive"))
      (node (ref "R59") (pin "2") (pinfunction "2_2") (pintype "passive"))
      (node (ref "R62") (pin "2") (pinfunction "2_2") (pintype "passive"))
    )
    (net (code "28") (name "Net-(C153-Pad2)") (class "Default")
      (node (ref "C153") (pin "2") (pinfunction "2_2") (pintype "passive"))
      (node (ref "FR15") (pin "1") (pinfunction "1_1") (pintype "passive"))
      (node (ref "R60") (pin "1") (pinfunction "1_1") (pintype "passive"))
    )
    (net (code "29") (name "Net-(C172-Pad1)") (class "Default")
      (node (ref "C172") (pin "1") (pinfunction "1_1") (pintype "passive"))
      (node (ref "J10") (pin "2") (pinfunction "2_2") (pintype "passive"))
      (node (ref "R69") (pin "2") (pinfunction "2_2") (pintype "passive"))
      (node (ref "R71") (pin "2") (pinfunction "2_2") (pintype "passive"))
    )
    (net (code "30") (name "Net-(IC7-CLKin)") (class "Default")
      (node (ref "C149") (pin "1") (pinfunction "1_1") (pintype "passive"))
      (node (ref "IC7") (pin "21") (pinfunction "CLKin_21") (pintype "passive"))
    )
    (net (code "31") (name "Net-(IC7-CLKin*)") (class "Default")
      (node (ref "C156") (pin "2") (pinfunction "2_2") (pintype "passive"))
      (node (ref "IC7") (pin "20") (pinfunction "CLKin*_20") (pintype "passive"))
    )
    (net (code "32") (name "Net-(IC7-CLKout0)") (class "Default")
      (node (ref "IC7") (pin "3") (pinfunction "CLKout0_3") (pintype "passive"))
      (node (ref "R61") (pin "2") (pinfunction "2_2") (pintype "passive"))
    )
    (net (code "33") (name "Net-(IC7-CLKout1)") (class "Default")
      (node (ref "IC7") (pin "5") (pinfunction "CLKout1_5") (pintype "passive"))
      (node (ref "R65") (pin "2") (pinfunction "2_2") (pintype "passive"))
    )
    (net (code "34") (name "Net-(IC7-OE)") (class "Default")
      (node (ref "IC7") (pin "24") (pinfunction "OE_24") (pintype "passive"))
      (node (ref "R57") (pin "1") (pinfunction "1_1") (pintype "passive"))
    )
    (net (code "35") (name "Net-(IC9-VDD)") (class "Default")
      (node (ref "C163") (pin "1") (pinfunction "1_1") (pintype "passive"))
      (node (ref "FR17") (pin "2") (pinfunction "2_2") (pintype "passive"))
      (node (ref "IC9") (pin "4") (pinfunction "VDD_4") (pintype "power_in"))
    )
    (net (code "36") (name "Net-(IC9-VOUT)") (class "Default")
      (node (ref "IC9") (pin "6") (pinfunction "VOUT_6") (pintype "tri_state"))
      (node (ref "R67") (pin "2") (pinfunction "2_2") (pintype "passive"))
    )
    (net (code "37") (name "Net-(IC12-FB)") (class "Default")
      (node (ref "IC12") (pin "11") (pinfunction "FB_11") (pintype "passive"))
      (node (ref "R83") (pin "2") (pinfunction "2_2") (pintype "passive"))
    )
    (net (code "38") (name "Net-(IC13-EN)") (class "Default")
      (node (ref "IC13") (pin "1") (pinfunction "EN_1") (pintype "passive"))
      (node (ref "R82") (pin "1") (pinfunction "1_1") (pintype "passive"))
      (node (ref "R84") (pin "2") (pinfunction "2_2") (pintype "passive"))
    )
    (net (code "39") (name "Net-(IC13-FB)") (class "Default")
      (node (ref "IC13") (pin "11") (pinfunction "FB_11") (pintype "passive"))
      (node (ref "R85") (pin "2") (pinfunction "2_2") (pintype "passive"))
    )
    (net (code "40") (name "Net-(IC13-PG)") (class "Default")
      (node (ref "IC13") (pin "10") (pinfunction "PG_10") (pintype "passive"))
      (node (ref "R78") (pin "1") (pinfunction "1_1") (pintype "passive"))
    )
    (net (code "41") (name "Net-(IC14-ADJ)") (class "Default")
      (node (ref "IC14") (pin "5") (pinfunction "ADJ_5") (pintype "input"))
      (node (ref "R80") (pin "1") (pinfunction "1_1") (pintype "passive"))
      (node (ref "R81") (pin "1") (pinfunction "1_1") (pintype "passive"))
    )
    (net (code "42") (name "Net-(IC14-PG)") (class "Default")
      (node (ref "C183") (pin "2") (pinfunction "2_2") (pintype "passive"))
      (node (ref "IC14") (pin "3") (pinfunction "PG_3") (pintype "output"))
    )
    (net (code "43") (name "Net-(IC14-Vout)") (class "Default")
      (node (ref "IC14") (pin "4") (pinfunction "Vout_4") (pintype "output"))
      (node (ref "R79") (pin "1") (pinfunction "1_1") (pintype "passive"))
      (node (ref "R80") (pin "2") (pinfunction "2_2") (pintype "passive"))
    )
    (net (code "44") (name "Net-(J10-Pad1)") (class "Default")
      (node (ref "J10") (pin "1") (pinfunction "1_1") (pintype "passive"))
      (node (ref "R74") (pin "2") (pinfunction "2_2") (pintype "passive"))
      (node (ref "VT4") (pin "D") (pinfunction "D_D") (pintype "passive"))
    )
    (net (code "45") (name "Net-(LED1-Pad3)") (class "Default")
      (node (ref "LED1") (pin "3") (pinfunction "3_3") (pintype "power_in"))
      (node (ref "R70") (pin "1") (pinfunction "1_1") (pintype "passive"))
    )
    (net (code "46") (name "Net-(LED1-Pad4)") (class "Default")
      (node (ref "LED1") (pin "4") (pinfunction "4_4") (pintype "power_in"))
      (node (ref "R72") (pin "1") (pinfunction "1_1") (pintype "passive"))
    )
    (net (code "47") (name "Net-(LED2-PadC1)") (class "Default")
      (node (ref "LED2") (pin "C1") (pinfunction "C1_C1") (pintype "power_in"))
      (node (ref "R75") (pin "1") (pinfunction "1_1") (pintype "passive"))
    )
    (net (code "48") (name "Net-(LED2-PadC2)") (class "Default")
      (node (ref "LED2") (pin "C2") (pinfunction "C2_C2") (pintype "power_in"))
      (node (ref "R73") (pin "1") (pinfunction "1_1") (pintype "passive"))
    )
    (net (code "49") (name "Net-(XO1-RF_OUT)") (class "Default")
      (node (ref "R59") (pin "1") (pinfunction "1_1") (pintype "passive"))
      (node (ref "XO1") (pin "6") (pinfunction "RF_OUT_6") (pintype "output"))
    )
    (net (code "50") (name "Net-(XO1-VCC)") (class "Default")
      (node (ref "C155") (pin "2") (pinfunction "2_2") (pintype "passive"))
      (node (ref "FR15") (pin "2") (pinfunction "2_2") (pintype "passive"))
      (node (ref "XO1") (pin "9") (pinfunction "VCC_9") (pintype "power_in"))
    )
    (net (code "51") (name "Net-(XO1-VC_FILTER)") (class "Default")
      (node (ref "C151") (pin "2") (pinfunction "2_2") (pintype "passive"))
      (node (ref "XO1") (pin "7") (pinfunction "VC_FILTER_7") (pintype "input"))
    )
    (net (code "52") (name "VCC1P8") (class "Default")
      (node (ref "C173") (pin "2") (pinfunction "2_2") (pintype "passive"))
      (node (ref "C174") (pin "1") (pinfunction "1_1") (pintype "passive"))
      (node (ref "C181") (pin "2") (pinfunction "2_2") (pintype "passive"))
      (node (ref "FR16") (pin "1") (pinfunction "1_1") (pintype "passive"))
      (node (ref "FR20") (pin "1") (pinfunction "1_1") (pintype "passive"))
      (node (ref "IC11") (pin "8") (pinfunction "VCC_8") (pintype "power_in"))
      (node (ref "IC12") (pin "7") (pinfunction "VOUT_7") (pintype "passive"))
      (node (ref "IC12") (pin "8") (pinfunction "VOUT_8") (pintype "passive"))
      (node (ref "R58") (pin "2") (pinfunction "2_2") (pintype "passive"))
    )
    (net (code "53") (name "VCC1P8_LMS") (class "Default")
      (node (ref "C175") (pin "2") (pinfunction "2_2") (pintype "passive"))
      (node (ref "FR20") (pin "2") (pinfunction "2_2") (pintype "passive"))
    )
    (net (code "54") (name "VCC3P3") (class "Default")
      (node (ref "C150") (pin "1") (pinfunction "1_1") (pintype "passive"))
      (node (ref "C162") (pin "1") (pinfunction "1_1") (pintype "passive"))
      (node (ref "C178") (pin "2") (pinfunction "2_2") (pintype "passive"))
      (node (ref "C182") (pin "2") (pinfunction "2_2") (pintype "passive"))
      (node (ref "FR22") (pin "1") (pinfunction "1_1") (pintype "passive"))
      (node (ref "IC10") (pin "8") (pinfunction "VCC_8") (pintype "power_in"))
      (node (ref "IC13") (pin "7") (pinfunction "VOUT_7") (pintype "passive"))
      (node (ref "IC13") (pin "8") (pinfunction "VOUT_8") (pintype "passive"))
      (node (ref "IC14") (pin "1") (pinfunction "EN_1") (pintype "input"))
      (node (ref "IC14") (pin "6") (pinfunction "Vin_6") (pintype "input"))
      (node (ref "IC8") (pin "8") (pinfunction "VCC_8") (pintype "passive"))
      (node (ref "LED1") (pin "1") (pinfunction "1_1") (pintype "power_in"))
      (node (ref "LED1") (pin "2") (pinfunction "2_2") (pintype "power_in"))
      (node (ref "LED2") (pin "A") (pinfunction "A_A") (pintype "power_in"))
      (node (ref "R64") (pin "1") (pinfunction "1_1") (pintype "passive"))
      (node (ref "R66") (pin "1") (pinfunction "1_1") (pintype "passive"))
      (node (ref "R71") (pin "1") (pinfunction "1_1") (pintype "passive"))
      (node (ref "R77") (pin "1") (pinfunction "1_1") (pintype "passive"))
    )
    (net (code "55") (name "VCC3P3_CLK") (class "Default")
      (node (ref "C184") (pin "2") (pinfunction "2_2") (pintype "passive"))
      (node (ref "FR17") (pin "1") (pinfunction "1_1") (pintype "passive"))
      (node (ref "FR19") (pin "1") (pinfunction "1_1") (pintype "passive"))
      (node (ref "FR22") (pin "2") (pinfunction "2_2") (pintype "passive"))
      (node (ref "R60") (pin "2") (pinfunction "2_2") (pintype "passive"))
    )
    (net (code "56") (name "VCC5P0_USB") (class "Default")
      (node (ref "C176") (pin "2") (pinfunction "2_2") (pintype "passive"))
      (node (ref "C177") (pin "2") (pinfunction "2_2") (pintype "passive"))
      (node (ref "IC12") (pin "1") (pinfunction "EN_1") (pintype "passive"))
      (node (ref "IC12") (pin "4") (pinfunction "VIN_4") (pintype "passive"))
      (node (ref "IC12") (pin "5") (pinfunction "VIN_5") (pintype "passive"))
      (node (ref "IC13") (pin "4") (pinfunction "VIN_4") (pintype "passive"))
      (node (ref "IC13") (pin "5") (pinfunction "VIN_5") (pintype "passive"))
      (node (ref "R69") (pin "1") (pinfunction "1_1") (pintype "passive"))
      (node (ref "R76") (pin "2") (pinfunction "2_2") (pintype "passive"))
      (node (ref "R78") (pin "2") (pinfunction "2_2") (pintype "passive"))
      (node (ref "R84") (pin "1") (pinfunction "1_1") (pintype "passive"))
    )
    (net (code "57") (name "VDIO_LMS") (class "Default")
      (node (ref "C180") (pin "2") (pinfunction "2_2") (pintype "passive"))
      (node (ref "FR21") (pin "2") (pinfunction "2_2") (pintype "passive"))
    )
    (net (code "58") (name "VDIO_LMS_FPGA") (class "Default")
      (node (ref "C179") (pin "2") (pinfunction "2_2") (pintype "passive"))
      (node (ref "FR18") (pin "1") (pinfunction "1_1") (pintype "passive"))
      (node (ref "FR21") (pin "1") (pinfunction "1_1") (pintype "passive"))
      (node (ref "R77") (pin "2") (pinfunction "2_2") (pintype "passive"))
      (node (ref "R79") (pin "2") (pinfunction "2_2") (pintype "passive"))
    )
    (net (code "59") (name "VDIO_LMS_LMK") (class "Default")
      (node (ref "C164") (pin "2") (pinfunction "2_2") (pintype "passive"))
      (node (ref "C165") (pin "2") (pinfunction "2_2") (pintype "passive"))
      (node (ref "C166") (pin "2") (pinfunction "2_2") (pintype "passive"))
      (node (ref "C167") (pin "2") (pinfunction "2_2") (pintype "passive"))
      (node (ref "FR18") (pin "2") (pinfunction "2_2") (pintype "passive"))
      (node (ref "IC7") (pin "14") (pinfunction "Vddo_14") (pintype "passive"))
      (node (ref "IC7") (pin "18") (pinfunction "Vddo_18") (pintype "passive"))
    )
    (net (code "60") (name "unconnected-(IC7-CLKout3-Pad15)") (class "Default")
      (node (ref "IC7") (pin "15") (pinfunction "CLKout3_15") (pintype "passive+no_connect"))
    )
    (net (code "61") (name "unconnected-(IC7-OSCin-Pad9)") (class "Default")
      (node (ref "IC7") (pin "9") (pinfunction "OSCin_9") (pintype "passive+no_connect"))
    )
    (net (code "62") (name "unconnected-(IC7-OSCout-Pad10)") (class "Default")
      (node (ref "IC7") (pin "10") (pinfunction "OSCout_10") (pintype "passive+no_connect"))
    )
    (net (code "63") (name "unconnected-(IC12-NC-Pad2)") (class "Default")
      (node (ref "IC12") (pin "2") (pinfunction "NC_2") (pintype "passive+no_connect"))
    )
    (net (code "64") (name "unconnected-(IC12-NC-Pad3)") (class "Default")
      (node (ref "IC12") (pin "3") (pinfunction "NC_3") (pintype "passive+no_connect"))
    )
    (net (code "65") (name "unconnected-(IC12-NC-Pad9)") (class "Default")
      (node (ref "IC12") (pin "9") (pinfunction "NC_9") (pintype "passive+no_connect"))
    )
    (net (code "66") (name "unconnected-(IC12-NC-Pad13)") (class "Default")
      (node (ref "IC12") (pin "13") (pinfunction "NC_13") (pintype "passive+no_connect"))
    )
    (net (code "67") (name "unconnected-(IC12-NC-Pad14)") (class "Default")
      (node (ref "IC12") (pin "14") (pinfunction "NC_14") (pintype "passive+no_connect"))
    )
    (net (code "68") (name "unconnected-(IC13-NC-Pad2)") (class "Default")
      (node (ref "IC13") (pin "2") (pinfunction "NC_2") (pintype "passive+no_connect"))
    )
    (net (code "69") (name "unconnected-(IC13-NC-Pad3)") (class "Default")
      (node (ref "IC13") (pin "3") (pinfunction "NC_3") (pintype "passive+no_connect"))
    )
    (net (code "70") (name "unconnected-(IC13-NC-Pad9)") (class "Default")
      (node (ref "IC13") (pin "9") (pinfunction "NC_9") (pintype "passive+no_connect"))
    )
    (net (code "71") (name "unconnected-(IC13-NC-Pad13)") (class "Default")
      (node (ref "IC13") (pin "13") (pinfunction "NC_13") (pintype "passive+no_connect"))
    )
    (net (code "72") (name "unconnected-(IC13-NC-Pad14)") (class "Default")
      (node (ref "IC13") (pin "14") (pinfunction "NC_14") (pintype "passive+no_connect"))
    )
    (net (code "73") (name "unconnected-(XO1-NC-Pad2)") (class "Default")
      (node (ref "XO1") (pin "2") (pinfunction "NC_2") (pintype "passive+no_connect"))
    )
    (net (code "74") (name "unconnected-(XO1-NC-Pad3)") (class "Default")
      (node (ref "XO1") (pin "3") (pinfunction "NC_3") (pintype "passive+no_connect"))
    )
    (net (code "75") (name "unconnected-(XO1-NC-Pad5)") (class "Default")
      (node (ref "XO1") (pin "5") (pinfunction "NC_5") (pintype "passive+no_connect"))
    )
    (net (code "76") (name "unconnected-(XO1-NC-Pad8)") (class "Default")
      (node (ref "XO1") (pin "8") (pinfunction "NC_8") (pintype "passive+no_connect"))
    )
    (net (code "77") (name "unconnected-(XO1-NC-Pad10)") (class "Default")
      (node (ref "XO1") (pin "10") (pinfunction "NC_10") (pintype "passive+no_connect"))
    )
  )
)
